# SW6208_A_B_C_L_LED__188.net
KiCad netlist of a schematic drawn in Altium Designer
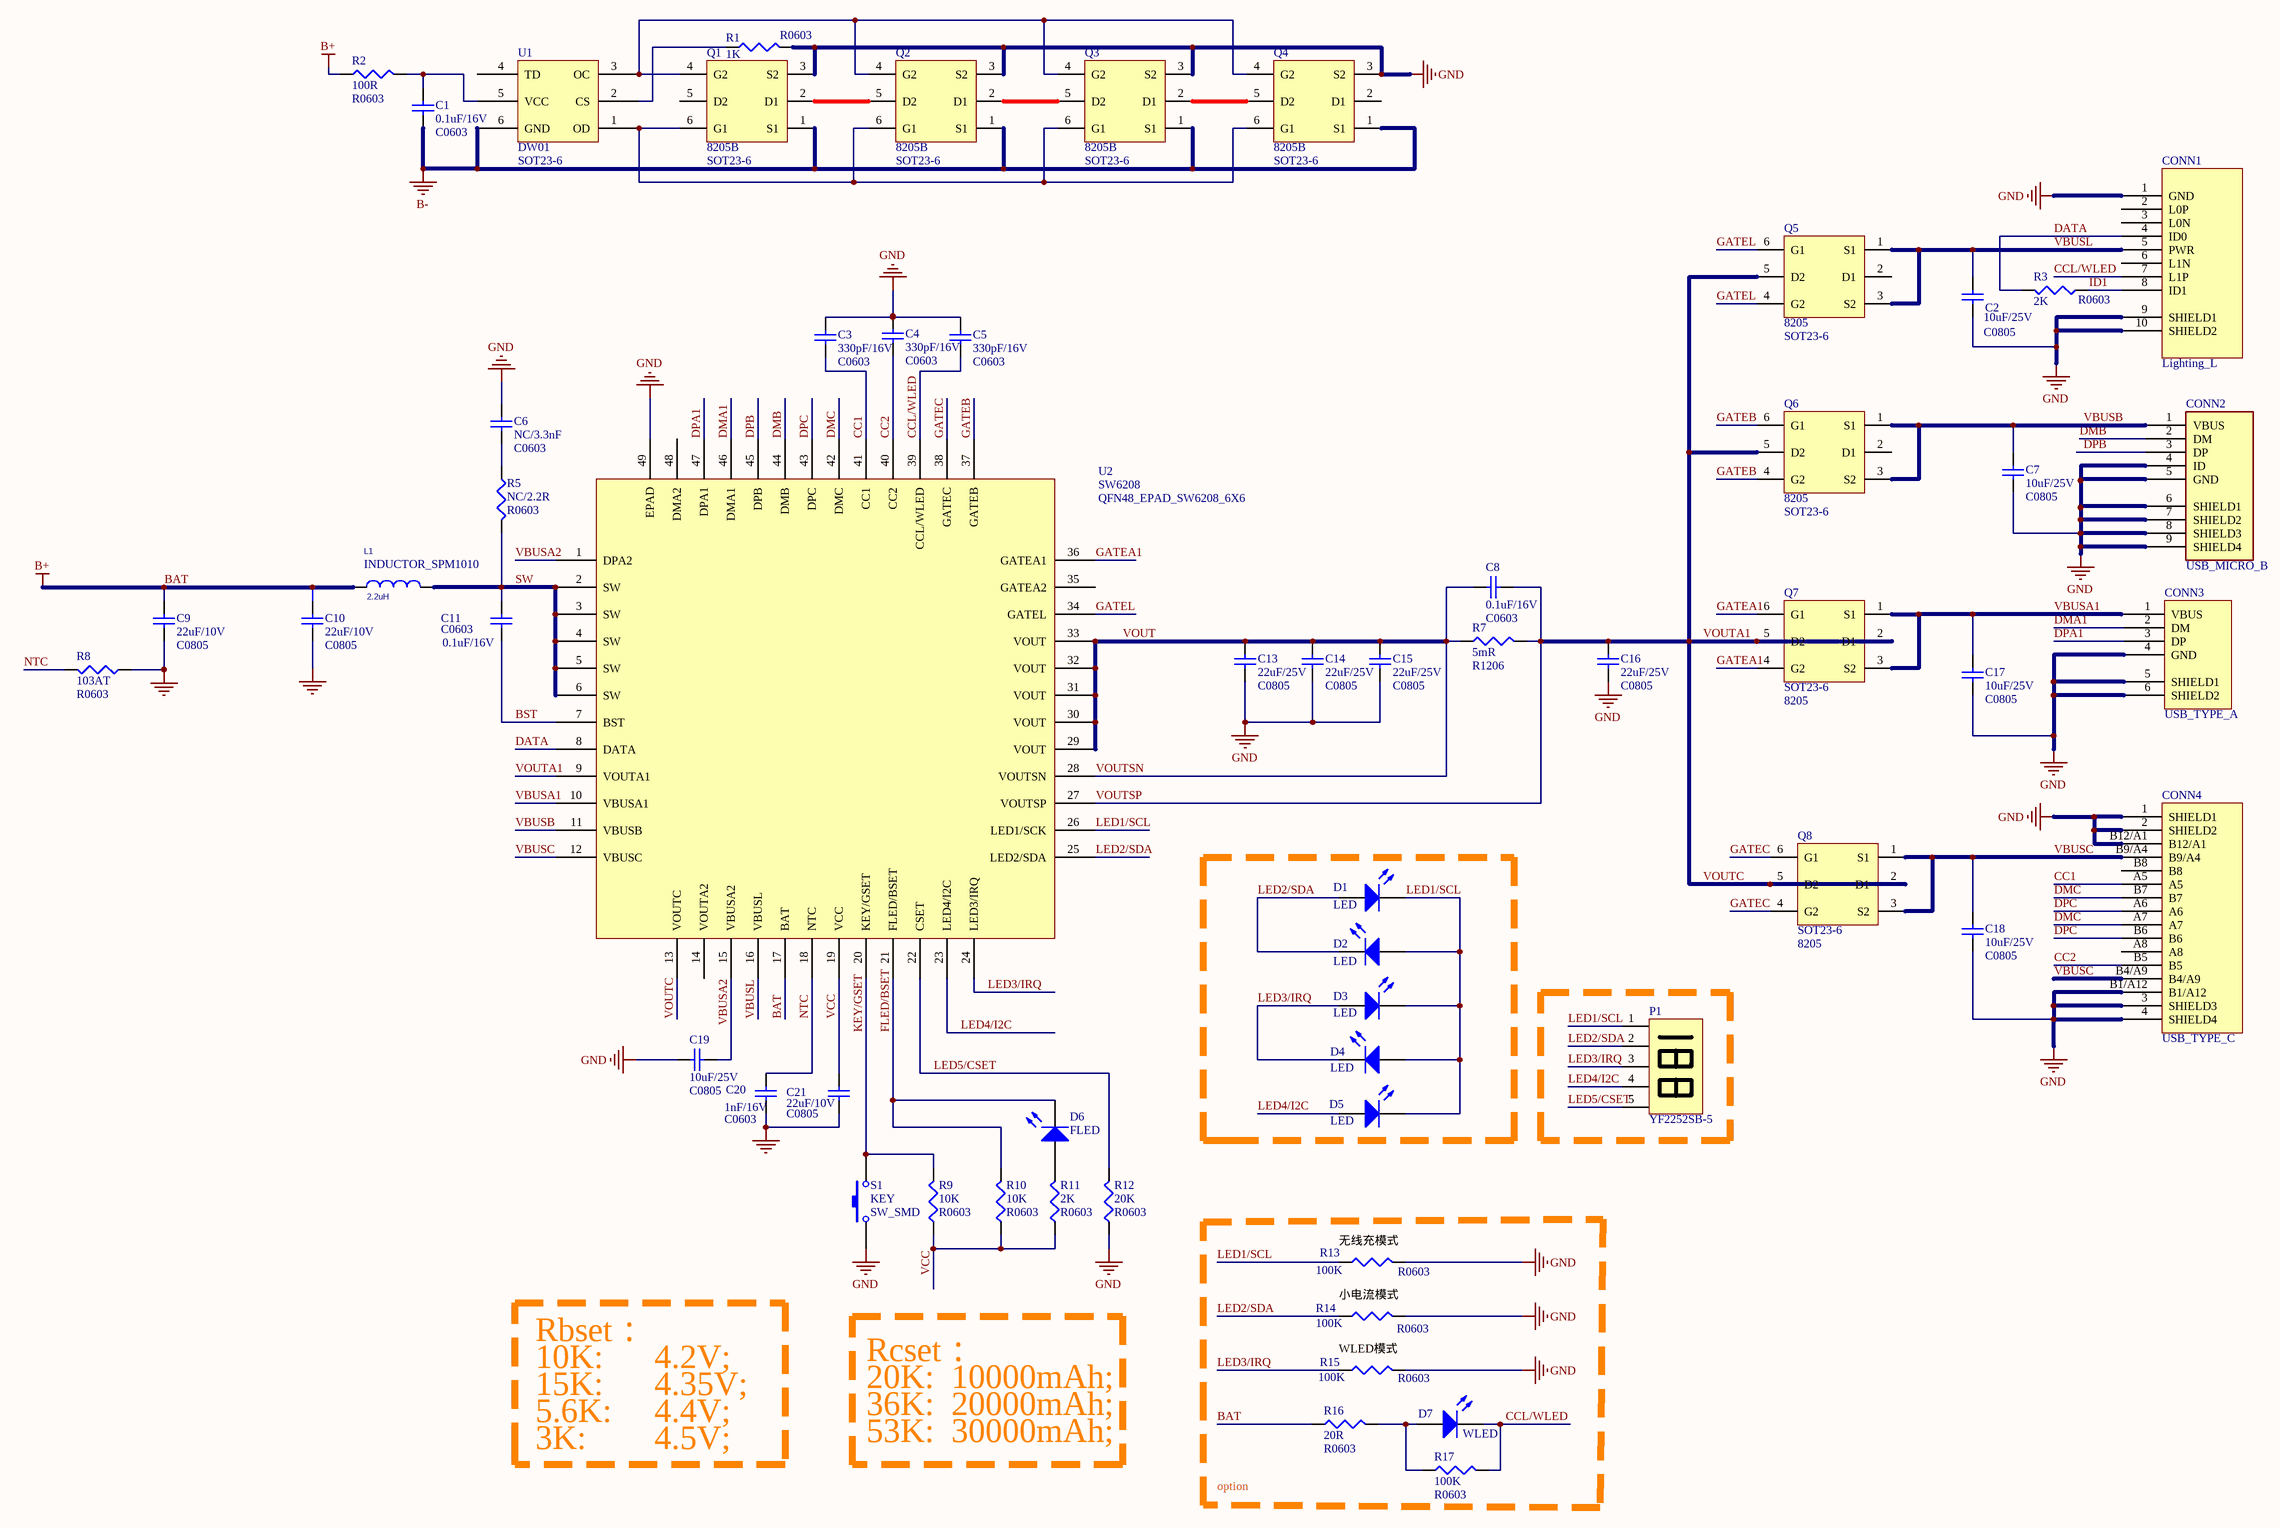
[diagram p0: SW6208+A+B+C+L+LED_普通188数码管.SchDoc]

(export (version "E")
  (design (tool "Eeschema 10.0.6"))
  (components
    (comp (ref "C1")
      (value "0.1uF/16V")
      (footprint "C0603")
      (description "Capacitor")
      (fields (field (name "PUBLISHER") "Altium Limited"))
      (libsource (lib "参考设计器件原理图更新") (part "CAP0603"))
    )
    (comp (ref "C2")
      (value "10uF/25V")
      (footprint "C0805")
      (description "Capacitor")
      (fields (field (name "PUBLISHER") "Altium Limited"))
      (libsource (lib "参考设计器件原理图更新") (part "CAP0805"))
    )
    (comp (ref "C3")
      (value "330pF/16V")
      (footprint "C0603")
      (description "Capacitor")
      (fields (field (name "PUBLISHER") "Altium Limited"))
      (libsource (lib "参考设计器件原理图更新") (part "CAP0603"))
    )
    (comp (ref "C4")
      (value "330pF/16V")
      (footprint "C0603")
      (description "Capacitor")
      (fields (field (name "PUBLISHER") "Altium Limited"))
      (libsource (lib "参考设计器件原理图更新") (part "CAP0603"))
    )
    (comp (ref "C5")
      (value "330pF/16V")
      (footprint "C0603")
      (description "Capacitor")
      (fields (field (name "PUBLISHER") "Altium Limited"))
      (libsource (lib "参考设计器件原理图更新") (part "CAP0603"))
    )
    (comp (ref "C6")
      (value "NC/3.3nF")
      (footprint "C0603")
      (description "Capacitor")
      (fields (field (name "PUBLISHER") "Altium Limited"))
      (libsource (lib "参考设计器件原理图更新") (part "CAP0603"))
    )
    (comp (ref "C7")
      (value "10uF/25V")
      (footprint "C0805")
      (description "Capacitor")
      (fields (field (name "PUBLISHER") "Altium Limited"))
      (libsource (lib "参考设计器件原理图更新") (part "CAP0805"))
    )
    (comp (ref "C8")
      (value "0.1uF/16V")
      (footprint "C0603")
      (description "Capacitor")
      (fields (field (name "PUBLISHER") "Altium Limited"))
      (libsource (lib "参考设计器件原理图更新") (part "CAP0603"))
    )
    (comp (ref "C9")
      (value "22uF/10V")
      (footprint "C0805")
      (description "Capacitor")
      (fields (field (name "PUBLISHER") "Altium Limited"))
      (libsource (lib "参考设计器件原理图更新") (part "CAP0805"))
    )
    (comp (ref "C10")
      (value "22uF/10V")
      (footprint "C0805")
      (description "Capacitor")
      (fields (field (name "PUBLISHER") "Altium Limited"))
      (libsource (lib "参考设计器件原理图更新") (part "CAP0805"))
    )
    (comp (ref "C11")
      (value "0.1uF/16V")
      (footprint "C0603")
      (description "Capacitor")
      (fields (field (name "PUBLISHER") "Altium Limited"))
      (libsource (lib "参考设计器件原理图更新") (part "CAP0603"))
    )
    (comp (ref "C13")
      (value "22uF/25V")
      (footprint "C0805")
      (description "Capacitor")
      (fields (field (name "PUBLISHER") "Altium Limited"))
      (libsource (lib "参考设计器件原理图更新") (part "CAP0805"))
    )
    (comp (ref "C14")
      (value "22uF/25V")
      (footprint "C0805")
      (description "Capacitor")
      (fields (field (name "PUBLISHER") "Altium Limited"))
      (libsource (lib "参考设计器件原理图更新") (part "CAP0805"))
    )
    (comp (ref "C15")
      (value "22uF/25V")
      (footprint "C0805")
      (description "Capacitor")
      (fields (field (name "PUBLISHER") "Altium Limited"))
      (libsource (lib "参考设计器件原理图更新") (part "CAP0805"))
    )
    (comp (ref "C16")
      (value "22uF/25V")
      (footprint "C0805")
      (description "Capacitor")
      (fields (field (name "PUBLISHER") "Altium Limited"))
      (libsource (lib "参考设计器件原理图更新") (part "CAP0805"))
    )
    (comp (ref "C17")
      (value "10uF/25V")
      (footprint "C0805")
      (description "Capacitor")
      (fields (field (name "PUBLISHER") "Altium Limited"))
      (libsource (lib "参考设计器件原理图更新") (part "CAP0805"))
    )
    (comp (ref "C18")
      (value "10uF/25V")
      (footprint "C0805")
      (description "Capacitor")
      (fields (field (name "PUBLISHER") "Altium Limited"))
      (libsource (lib "参考设计器件原理图更新") (part "CAP0805"))
    )
    (comp (ref "C19")
      (value "10uF/25V")
      (footprint "C0805")
      (description "Capacitor")
      (fields (field (name "PUBLISHER") "Altium Limited"))
      (libsource (lib "参考设计器件原理图更新") (part "CAP0805"))
    )
    (comp (ref "C20")
      (value "1nF/16V")
      (footprint "C0603")
      (description "Capacitor")
      (fields (field (name "PUBLISHER") "Altium Limited"))
      (libsource (lib "参考设计器件原理图更新") (part "CAP0603"))
    )
    (comp (ref "C21")
      (value "22uF/10V")
      (footprint "C0805")
      (description "Capacitor")
      (fields (field (name "PUBLISHER") "Altium Limited"))
      (libsource (lib "参考设计器件原理图更新") (part "CAP0805"))
    )
    (comp (ref "CONN1")
      (value "Lighting_L")
      (footprint "Lighting")
      (libsource (lib "参考设计器件原理图更新") (part "LIGHTING_PORT"))
    )
    (comp (ref "CONN2")
      (value "USB_MICRO_B")
      (footprint "USB_MICRO_B")
      (libsource (lib "参考设计器件原理图更新") (part "USB_MICRO_B"))
    )
    (comp (ref "CONN3")
      (value "USB_TYPE_A")
      (footprint "USB_TYPE_A")
      (libsource (lib "参考设计器件原理图更新") (part "USB_TYPE_A"))
    )
    (comp (ref "CONN4")
      (value "USB_TYPE_C")
      (footprint "LOUISAD:USB_TYPE_C")
      (libsource (lib "参考设计器件原理图更新") (part "USB_TYPE_C"))
    )
    (comp (ref "D1")
      (value "LED")
      (footprint "LED0603")
      (fields (field (name "PUBLISHER") "Altium Limited"))
      (libsource (lib "参考设计器件原理图更新") (part "LED_0603"))
    )
    (comp (ref "D2")
      (value "LED")
      (footprint "LED0603")
      (fields (field (name "PUBLISHER") "Altium Limited"))
      (libsource (lib "参考设计器件原理图更新") (part "LED_0603"))
    )
    (comp (ref "D3")
      (value "LED")
      (footprint "LED0603")
      (fields (field (name "PUBLISHER") "Altium Limited"))
      (libsource (lib "参考设计器件原理图更新") (part "LED_0603"))
    )
    (comp (ref "D4")
      (value "LED")
      (footprint "LED0603")
      (fields (field (name "PUBLISHER") "Altium Limited"))
      (libsource (lib "参考设计器件原理图更新") (part "LED_0603"))
    )
    (comp (ref "D5")
      (value "LED")
      (footprint "LED0603")
      (fields (field (name "PUBLISHER") "Altium Limited"))
      (libsource (lib "参考设计器件原理图更新") (part "LED_0603"))
    )
    (comp (ref "D6")
      (value "FLED")
      (footprint "LED0603")
      (description "LED")
      (fields (field (name "PUBLISHER") "Altium Limited"))
      (libsource (lib "参考设计器件原理图更新") (part "LED_0603"))
    )
    (comp (ref "D7")
      (value "WLED")
      (footprint "LED_5MM")
      (fields (field (name "PUBLISHER") "Altium Limited"))
      (libsource (lib "参考设计器件原理图更新") (part "WLED"))
    )
    (comp (ref "L1")
      (value "2.2uH")
      (footprint "INDUCTOR_SPM1010")
      (description "INDUCTOR")
      (libsource (lib "参考设计器件原理图更新") (part "INDUCTOR_SPM1010"))
    )
    (comp (ref "P1")
      (value "YF2252SB-5")
      (footprint "LED_Display_5")
      (description "188_LED_Display")
      (libsource (lib "参考设计器件原理图更新") (part "LED_Display_5"))
    )
    (comp (ref "Q1")
      (value "8205B")
      (footprint "SOT23-6")
      (description "NMOS")
      (fields (field (name "FOOTPRINF") "SOT23-6"))
      (libsource (lib "") (part "8205_1"))
    )
    (comp (ref "Q2")
      (value "8205B")
      (footprint "SOT23-6")
      (description "NMOS")
      (fields (field (name "FOOTPRINF") "SOT23-6"))
      (libsource (lib "") (part "8205_1"))
    )
    (comp (ref "Q3")
      (value "8205B")
      (footprint "SOT23-6")
      (description "NMOS")
      (fields (field (name "FOOTPRINF") "SOT23-6"))
      (libsource (lib "") (part "8205_1"))
    )
    (comp (ref "Q4")
      (value "8205B")
      (footprint "SOT23-6")
      (description "NMOS")
      (fields (field (name "FOOTPRINF") "SOT23-6"))
      (libsource (lib "") (part "8205_1"))
    )
    (comp (ref "Q5")
      (value "8205")
      (footprint "SOT23-6")
      (description "NMOS")
      (fields (field (name "FOOTPRINF") "SOT23-6"))
      (libsource (lib "参考设计器件原理图更新") (part "8205"))
    )
    (comp (ref "Q6")
      (value "8205")
      (footprint "SOT23-6")
      (description "NMOS")
      (fields (field (name "FOOTPRINF") "SOT23-6"))
      (libsource (lib "参考设计器件原理图更新") (part "8205"))
    )
    (comp (ref "Q7")
      (value "8205")
      (footprint "SOT-23-6")
      (fields (field (name "FOOTPRINF") "SOT23-6"))
      (libsource (lib "*") (part "8205B"))
    )
    (comp (ref "Q8")
      (value "8205")
      (footprint "SOT-23-6")
      (fields (field (name "FOOTPRINF") "SOT23-6"))
      (libsource (lib "*") (part "8205B"))
    )
    (comp (ref "R1")
      (value "1K")
      (footprint "R0603")
      (description "Resistor")
      (fields (field (name "PUBLISHER") "Altium Limited"))
      (libsource (lib "参考设计器件原理图更新") (part "RES_0603"))
    )
    (comp (ref "R2")
      (value "100R")
      (footprint "R0603")
      (description "Resistor")
      (fields (field (name "PUBLISHER") "Altium Limited"))
      (libsource (lib "参考设计器件原理图更新") (part "RES_0603"))
    )
    (comp (ref "R3")
      (value "2K")
      (footprint "R0603")
      (description "Resistor")
      (fields (field (name "PUBLISHER") "Altium Limited"))
      (libsource (lib "参考设计器件原理图更新") (part "RES_0603"))
    )
    (comp (ref "R5")
      (value "NC/2.2R")
      (footprint "R0603")
      (description "Resistor")
      (fields (field (name "PUBLISHER") "Altium Limited"))
      (libsource (lib "参考设计器件原理图更新") (part "RES_0603"))
    )
    (comp (ref "R7")
      (value "5mR")
      (footprint "R1206")
      (description "Resistor")
      (fields (field (name "PUBLISHER") "Altium Limited"))
      (libsource (lib "参考设计器件原理图更新") (part "RES_1206"))
    )
    (comp (ref "R8")
      (value "103AT")
      (footprint "R0603")
      (description "Resistor")
      (fields (field (name "PUBLISHER") "Altium Limited"))
      (libsource (lib "参考设计器件原理图更新") (part "RES_0603"))
    )
    (comp (ref "R9")
      (value "10K")
      (footprint "R0603")
      (description "Resistor")
      (fields (field (name "PUBLISHER") "Altium Limited"))
      (libsource (lib "参考设计器件原理图更新") (part "RES_0603"))
    )
    (comp (ref "R10")
      (value "10K")
      (footprint "R0603")
      (description "Resistor")
      (fields (field (name "PUBLISHER") "Altium Limited"))
      (libsource (lib "参考设计器件原理图更新") (part "RES_0603"))
    )
    (comp (ref "R11")
      (value "2K")
      (footprint "R0603")
      (description "Resistor")
      (fields (field (name "PUBLISHER") "Altium Limited"))
      (libsource (lib "参考设计器件原理图更新") (part "RES_0603"))
    )
    (comp (ref "R12")
      (value "20K")
      (footprint "R0603")
      (description "Resistor")
      (fields (field (name "PUBLISHER") "Altium Limited"))
      (libsource (lib "参考设计器件原理图更新") (part "RES_0603"))
    )
    (comp (ref "R13")
      (value "100K")
      (footprint "R0603")
      (description "Resistor")
      (fields (field (name "PUBLISHER") "Altium Limited"))
      (libsource (lib "参考设计器件原理图更新") (part "RES_0603"))
    )
    (comp (ref "R14")
      (value "100K")
      (footprint "R0603")
      (description "Resistor")
      (fields (field (name "PUBLISHER") "Altium Limited"))
      (libsource (lib "参考设计器件原理图更新") (part "RES_0603"))
    )
    (comp (ref "R15")
      (value "100K")
      (footprint "R0603")
      (description "Resistor")
      (fields (field (name "PUBLISHER") "Altium Limited"))
      (libsource (lib "参考设计器件原理图更新") (part "RES_0603"))
    )
    (comp (ref "R16")
      (value "20R")
      (footprint "R0603")
      (description "Resistor")
      (fields (field (name "PUBLISHER") "Altium Limited"))
      (libsource (lib "参考设计器件原理图更新") (part "RES_0603"))
    )
    (comp (ref "R17")
      (value "100K")
      (footprint "R0603")
      (description "Resistor")
      (fields (field (name "PUBLISHER") "Altium Limited"))
      (libsource (lib "参考设计器件原理图更新") (part "RES_0603"))
    )
    (comp (ref "S1")
      (value "KEY")
      (footprint "SW_SMD")
      (fields (field (name "FOOTPRINF") "SW_SMD"))
      (libsource (lib "参考设计器件原理图更新") (part "SW K"))
    )
    (comp (ref "U1")
      (value "DW01")
      (footprint "SOT23-6")
      (description "BAT_PROTECT_IC")
      (libsource (lib "参考设计器件原理图更新") (part "DW01"))
    )
    (comp (ref "U2")
      (value "SW6208")
      (footprint "QFN48_EPAD_SW6208_6X6")
      (description "IC")
      (libsource (lib "芯片型号原理图") (part "SW6208"))
    )
  )
  (nets
    (net (code "1") (name "/BST") (class "Default")
      (node (ref "C11") (pin "1") (pinfunction "1_1") (pintype "passive"))
      (node (ref "U2") (pin "7") (pinfunction "BST_7") (pintype "passive"))
    )
    (net (code "2") (name "/CC1") (class "Default")
      (node (ref "C3") (pin "1") (pinfunction "1_1") (pintype "passive"))
      (node (ref "CONN4") (pin "A5") (pinfunction "A5_A5") (pintype "passive"))
      (node (ref "U2") (pin "41") (pinfunction "CC1_41") (pintype "passive"))
    )
    (net (code "3") (name "/CC2") (class "Default")
      (node (ref "C4") (pin "1") (pinfunction "1_1") (pintype "passive"))
      (node (ref "CONN4") (pin "B5") (pinfunction "B5_B5") (pintype "passive"))
      (node (ref "U2") (pin "40") (pinfunction "CC2_40") (pintype "passive"))
    )
    (net (code "4") (name "/CCL{slash}WLED") (class "Default")
      (node (ref "C5") (pin "1") (pinfunction "1_1") (pintype "passive"))
      (node (ref "CONN1") (pin "7") (pinfunction "L1P_7") (pintype "passive"))
      (node (ref "D7") (pin "2") (pinfunction "K_2") (pintype "passive"))
      (node (ref "R17") (pin "2") (pinfunction "2_2") (pintype "passive"))
      (node (ref "U2") (pin "39") (pinfunction "CCL/WLED_39") (pintype "passive"))
    )
    (net (code "5") (name "/DATA") (class "Default")
      (node (ref "CONN1") (pin "4") (pinfunction "ID0_4") (pintype "passive"))
      (node (ref "R3") (pin "2") (pinfunction "2_2") (pintype "passive"))
      (node (ref "U2") (pin "8") (pinfunction "DATA_8") (pintype "passive"))
    )
    (net (code "6") (name "/DMA1") (class "Default")
      (node (ref "CONN3") (pin "2") (pinfunction "DM_2") (pintype "passive"))
      (node (ref "U2") (pin "46") (pinfunction "DMA1_46") (pintype "passive"))
    )
    (net (code "7") (name "/DMB") (class "Default")
      (node (ref "CONN2") (pin "2") (pinfunction "DM_2") (pintype "passive"))
      (node (ref "U2") (pin "44") (pinfunction "DMB_44") (pintype "passive"))
    )
    (net (code "8") (name "/DMC") (class "Default")
      (node (ref "CONN4") (pin "A7") (pinfunction "A7_A7") (pintype "passive"))
      (node (ref "CONN4") (pin "B7") (pinfunction "B7_B7") (pintype "passive"))
      (node (ref "U2") (pin "42") (pinfunction "DMC_42") (pintype "passive"))
    )
    (net (code "9") (name "/DPA1") (class "Default")
      (node (ref "CONN3") (pin "3") (pinfunction "DP_3") (pintype "passive"))
      (node (ref "U2") (pin "47") (pinfunction "DPA1_47") (pintype "passive"))
    )
    (net (code "10") (name "/DPB") (class "Default")
      (node (ref "CONN2") (pin "3") (pinfunction "DP_3") (pintype "passive"))
      (node (ref "U2") (pin "45") (pinfunction "DPB_45") (pintype "passive"))
    )
    (net (code "11") (name "/DPC") (class "Default")
      (node (ref "CONN4") (pin "A6") (pinfunction "A6_A6") (pintype "passive"))
      (node (ref "CONN4") (pin "B6") (pinfunction "B6_B6") (pintype "passive"))
      (node (ref "U2") (pin "43") (pinfunction "DPC_43") (pintype "passive"))
    )
    (net (code "12") (name "/FLED{slash}BSET") (class "Default")
      (node (ref "D6") (pin "2") (pinfunction "K_2") (pintype "passive"))
      (node (ref "R10") (pin "2") (pinfunction "2_2") (pintype "passive"))
      (node (ref "U2") (pin "21") (pinfunction "FLED/BSET_21") (pintype "passive"))
    )
    (net (code "13") (name "/GATEA1") (class "Default")
      (node (ref "Q7") (pin "4") (pinfunction "G2_4") (pintype "passive"))
      (node (ref "Q7") (pin "6") (pinfunction "G1_6") (pintype "passive"))
      (node (ref "U2") (pin "36") (pinfunction "GATEA1_36") (pintype "passive"))
    )
    (net (code "14") (name "/GATEB") (class "Default")
      (node (ref "Q6") (pin "4") (pinfunction "G2_4") (pintype "passive"))
      (node (ref "Q6") (pin "6") (pinfunction "G1_6") (pintype "passive"))
      (node (ref "U2") (pin "37") (pinfunction "GATEB_37") (pintype "passive"))
    )
    (net (code "15") (name "/GATEC") (class "Default")
      (node (ref "Q8") (pin "4") (pinfunction "G2_4") (pintype "passive"))
      (node (ref "Q8") (pin "6") (pinfunction "G1_6") (pintype "passive"))
      (node (ref "U2") (pin "38") (pinfunction "GATEC_38") (pintype "passive"))
    )
    (net (code "16") (name "/GATEL") (class "Default")
      (node (ref "Q5") (pin "4") (pinfunction "G2_4") (pintype "passive"))
      (node (ref "Q5") (pin "6") (pinfunction "G1_6") (pintype "passive"))
      (node (ref "U2") (pin "34") (pinfunction "GATEL_34") (pintype "passive"))
    )
    (net (code "17") (name "/ID1") (class "Default")
      (node (ref "CONN1") (pin "8") (pinfunction "ID1_8") (pintype "passive"))
      (node (ref "R3") (pin "1") (pinfunction "1_1") (pintype "passive"))
    )
    (net (code "18") (name "/KEY{slash}GSET") (class "Default")
      (node (ref "R9") (pin "2") (pinfunction "2_2") (pintype "passive"))
      (node (ref "S1") (pin "2") (pinfunction "2_2") (pintype "passive"))
      (node (ref "U2") (pin "20") (pinfunction "KEY/GSET_20") (pintype "passive"))
    )
    (net (code "19") (name "/LED1{slash}SCL") (class "Default")
      (node (ref "D1") (pin "2") (pinfunction "K_2") (pintype "passive"))
      (node (ref "D2") (pin "1") (pinfunction "A_1") (pintype "passive"))
      (node (ref "D3") (pin "2") (pinfunction "K_2") (pintype "passive"))
      (node (ref "D4") (pin "1") (pinfunction "A_1") (pintype "passive"))
      (node (ref "D5") (pin "2") (pinfunction "K_2") (pintype "passive"))
      (node (ref "P1") (pin "1") (pinfunction "F_1") (pintype "passive"))
      (node (ref "R13") (pin "1") (pinfunction "1_1") (pintype "passive"))
      (node (ref "U2") (pin "26") (pinfunction "LED1/SCK_26") (pintype "passive"))
    )
    (net (code "20") (name "/LED2{slash}SDA") (class "Default")
      (node (ref "D1") (pin "1") (pinfunction "A_1") (pintype "passive"))
      (node (ref "D2") (pin "2") (pinfunction "K_2") (pintype "passive"))
      (node (ref "P1") (pin "2") (pinfunction "C_2") (pintype "passive"))
      (node (ref "R14") (pin "1") (pinfunction "1_1") (pintype "passive"))
      (node (ref "U2") (pin "25") (pinfunction "LED2/SDA_25") (pintype "passive"))
    )
    (net (code "21") (name "/LED3{slash}IRQ") (class "Default")
      (node (ref "D3") (pin "1") (pinfunction "A_1") (pintype "passive"))
      (node (ref "D4") (pin "2") (pinfunction "K_2") (pintype "passive"))
      (node (ref "P1") (pin "3") (pinfunction "D_3") (pintype "passive"))
      (node (ref "R15") (pin "1") (pinfunction "1_1") (pintype "passive"))
      (node (ref "U2") (pin "24") (pinfunction "LED3/IRQ_24") (pintype "passive"))
    )
    (net (code "22") (name "/LED4{slash}I2C") (class "Default")
      (node (ref "D5") (pin "1") (pinfunction "A_1") (pintype "passive"))
      (node (ref "P1") (pin "4") (pinfunction "E_4") (pintype "passive"))
      (node (ref "U2") (pin "23") (pinfunction "LED4/I2C_23") (pintype "passive"))
    )
    (net (code "23") (name "/LED5{slash}CSET") (class "Default")
      (node (ref "P1") (pin "5") (pinfunction "G_5") (pintype "passive"))
      (node (ref "R12") (pin "2") (pinfunction "2_2") (pintype "passive"))
      (node (ref "U2") (pin "22") (pinfunction "CSET_22") (pintype "passive"))
    )
    (net (code "24") (name "/NTC") (class "Default")
      (node (ref "C20") (pin "1") (pinfunction "1_1") (pintype "passive"))
      (node (ref "R8") (pin "2") (pinfunction "2_2") (pintype "passive"))
      (node (ref "U2") (pin "18") (pinfunction "NTC_18") (pintype "passive"))
    )
    (net (code "25") (name "/SW") (class "Default")
      (node (ref "C11") (pin "2") (pinfunction "2_2") (pintype "passive"))
      (node (ref "L1") (pin "2") (pinfunction "2_2") (pintype "passive"))
      (node (ref "R5") (pin "2") (pinfunction "2_2") (pintype "passive"))
      (node (ref "U2") (pin "2") (pinfunction "SW_2") (pintype "passive"))
      (node (ref "U2") (pin "3") (pinfunction "SW_3") (pintype "passive"))
      (node (ref "U2") (pin "4") (pinfunction "SW_4") (pintype "passive"))
      (node (ref "U2") (pin "5") (pinfunction "SW_5") (pintype "passive"))
      (node (ref "U2") (pin "6") (pinfunction "SW_6") (pintype "passive"))
    )
    (net (code "26") (name "/VBUSA1") (class "Default")
      (node (ref "C17") (pin "2") (pinfunction "2_2") (pintype "passive"))
      (node (ref "Q7") (pin "1") (pinfunction "S1_1") (pintype "passive"))
      (node (ref "Q7") (pin "3") (pinfunction "S2_3") (pintype "passive"))
      (node (ref "U2") (pin "10") (pinfunction "VBUSA1_10") (pintype "passive"))
    )
    (net (code "27") (name "/VBUSA2") (class "Default")
      (node (ref "C19") (pin "2") (pinfunction "2_2") (pintype "passive"))
      (node (ref "U2") (pin "1") (pinfunction "DPA2_1") (pintype "passive"))
      (node (ref "U2") (pin "15") (pinfunction "VBUSA2_15") (pintype "passive"))
    )
    (net (code "28") (name "/VBUSB") (class "Default")
      (node (ref "C7") (pin "2") (pinfunction "2_2") (pintype "passive"))
      (node (ref "CONN2") (pin "1") (pinfunction "VBUS_1") (pintype "passive"))
      (node (ref "Q6") (pin "1") (pinfunction "S1_1") (pintype "passive"))
      (node (ref "Q6") (pin "3") (pinfunction "S2_3") (pintype "passive"))
      (node (ref "U2") (pin "11") (pinfunction "VBUSB_11") (pintype "passive"))
    )
    (net (code "29") (name "/VBUSC") (class "Default")
      (node (ref "C18") (pin "2") (pinfunction "2_2") (pintype "passive"))
      (node (ref "CONN4") (pin "B4/A9") (pinfunction "B4/A9_B4/A9") (pintype "passive"))
      (node (ref "CONN4") (pin "B9/A4") (pinfunction "B9/A4_B9/A4") (pintype "passive"))
      (node (ref "Q8") (pin "1") (pinfunction "S1_1") (pintype "passive"))
      (node (ref "Q8") (pin "3") (pinfunction "S2_3") (pintype "passive"))
      (node (ref "U2") (pin "12") (pinfunction "VBUSC_12") (pintype "passive"))
    )
    (net (code "30") (name "/VBUSL") (class "Default")
      (node (ref "C2") (pin "2") (pinfunction "2_2") (pintype "passive"))
      (node (ref "CONN1") (pin "5") (pinfunction "PWR_5") (pintype "passive"))
      (node (ref "Q5") (pin "1") (pinfunction "S1_1") (pintype "passive"))
      (node (ref "Q5") (pin "3") (pinfunction "S2_3") (pintype "passive"))
      (node (ref "U2") (pin "16") (pinfunction "VBUSL_16") (pintype "passive"))
    )
    (net (code "31") (name "/VCC") (class "Default")
      (node (ref "C21") (pin "1") (pinfunction "1_1") (pintype "passive"))
      (node (ref "R10") (pin "1") (pinfunction "1_1") (pintype "passive"))
      (node (ref "R11") (pin "1") (pinfunction "1_1") (pintype "passive"))
      (node (ref "R9") (pin "1") (pinfunction "1_1") (pintype "passive"))
      (node (ref "U2") (pin "19") (pinfunction "VCC_19") (pintype "passive"))
    )
    (net (code "32") (name "/VOUT") (class "Default")
      (node (ref "C13") (pin "2") (pinfunction "2_2") (pintype "passive"))
      (node (ref "C14") (pin "2") (pinfunction "2_2") (pintype "passive"))
      (node (ref "C15") (pin "2") (pinfunction "2_2") (pintype "passive"))
      (node (ref "C8") (pin "1") (pinfunction "1_1") (pintype "passive"))
      (node (ref "R7") (pin "1") (pinfunction "1_1") (pintype "passive"))
      (node (ref "U2") (pin "28") (pinfunction "VOUTSN_28") (pintype "passive"))
      (node (ref "U2") (pin "29") (pinfunction "VOUT_29") (pintype "passive"))
      (node (ref "U2") (pin "30") (pinfunction "VOUT_30") (pintype "passive"))
      (node (ref "U2") (pin "31") (pinfunction "VOUT_31") (pintype "passive"))
      (node (ref "U2") (pin "32") (pinfunction "VOUT_32") (pintype "passive"))
      (node (ref "U2") (pin "33") (pinfunction "VOUT_33") (pintype "passive"))
    )
    (net (code "33") (name "/VOUTA1") (class "Default")
      (node (ref "C16") (pin "2") (pinfunction "2_2") (pintype "passive"))
      (node (ref "C8") (pin "2") (pinfunction "2_2") (pintype "passive"))
      (node (ref "Q5") (pin "5") (pinfunction "D2_5") (pintype "passive"))
      (node (ref "Q6") (pin "5") (pinfunction "D2_5") (pintype "passive"))
      (node (ref "Q7") (pin "2") (pinfunction "D1_2") (pintype "passive"))
      (node (ref "Q7") (pin "5") (pinfunction "D2_5") (pintype "passive"))
      (node (ref "Q8") (pin "2") (pinfunction "D1_2") (pintype "passive"))
      (node (ref "Q8") (pin "5") (pinfunction "D2_5") (pintype "passive"))
      (node (ref "R7") (pin "2") (pinfunction "2_2") (pintype "passive"))
      (node (ref "U2") (pin "13") (pinfunction "VOUTC_13") (pintype "passive"))
      (node (ref "U2") (pin "27") (pinfunction "VOUTSP_27") (pintype "passive"))
      (node (ref "U2") (pin "9") (pinfunction "VOUTA1_9") (pintype "passive"))
    )
    (net (code "34") (name "B+") (class "Default")
      (node (ref "C10") (pin "2") (pinfunction "2_2") (pintype "passive"))
      (node (ref "C9") (pin "2") (pinfunction "2_2") (pintype "passive"))
      (node (ref "L1") (pin "1") (pinfunction "1_1") (pintype "passive"))
      (node (ref "R16") (pin "1") (pinfunction "1_1") (pintype "passive"))
      (node (ref "R2") (pin "1") (pinfunction "1_1") (pintype "passive"))
      (node (ref "U2") (pin "17") (pinfunction "BAT_17") (pintype "passive"))
    )
    (net (code "35") (name "B-") (class "Default")
      (node (ref "C1") (pin "1") (pinfunction "1_1") (pintype "passive"))
      (node (ref "Q1") (pin "1") (pinfunction "S1_1") (pintype "passive"))
      (node (ref "Q2") (pin "1") (pinfunction "S1_1") (pintype "passive"))
      (node (ref "Q3") (pin "1") (pinfunction "S1_1") (pintype "passive"))
      (node (ref "Q4") (pin "1") (pinfunction "S1_1") (pintype "passive"))
      (node (ref "U1") (pin "6") (pinfunction "GND_6") (pintype "passive"))
    )
    (net (code "36") (name "GND") (class "Default")
      (node (ref "C10") (pin "1") (pinfunction "1_1") (pintype "passive"))
      (node (ref "C13") (pin "1") (pinfunction "1_1") (pintype "passive"))
      (node (ref "C14") (pin "1") (pinfunction "1_1") (pintype "passive"))
      (node (ref "C15") (pin "1") (pinfunction "1_1") (pintype "passive"))
      (node (ref "C16") (pin "1") (pinfunction "1_1") (pintype "passive"))
      (node (ref "C17") (pin "1") (pinfunction "1_1") (pintype "passive"))
      (node (ref "C18") (pin "1") (pinfunction "1_1") (pintype "passive"))
      (node (ref "C19") (pin "1") (pinfunction "1_1") (pintype "passive"))
      (node (ref "C2") (pin "1") (pinfunction "1_1") (pintype "passive"))
      (node (ref "C20") (pin "2") (pinfunction "2_2") (pintype "passive"))
      (node (ref "C21") (pin "2") (pinfunction "2_2") (pintype "passive"))
      (node (ref "C3") (pin "2") (pinfunction "2_2") (pintype "passive"))
      (node (ref "C4") (pin "2") (pinfunction "2_2") (pintype "passive"))
      (node (ref "C5") (pin "2") (pinfunction "2_2") (pintype "passive"))
      (node (ref "C6") (pin "2") (pinfunction "2_2") (pintype "passive"))
      (node (ref "C7") (pin "1") (pinfunction "1_1") (pintype "passive"))
      (node (ref "C9") (pin "1") (pinfunction "1_1") (pintype "passive"))
      (node (ref "CONN1") (pin "1") (pinfunction "GND_1") (pintype "passive"))
      (node (ref "CONN1") (pin "10") (pinfunction "SHIELD2_10") (pintype "passive"))
      (node (ref "CONN1") (pin "9") (pinfunction "SHIELD1_9") (pintype "passive"))
      (node (ref "CONN2") (pin "4") (pinfunction "ID_4") (pintype "passive"))
      (node (ref "CONN2") (pin "5") (pinfunction "GND_5") (pintype "passive"))
      (node (ref "CONN2") (pin "6") (pinfunction "SHIELD1_6") (pintype "passive"))
      (node (ref "CONN2") (pin "7") (pinfunction "SHIELD2_7") (pintype "passive"))
      (node (ref "CONN2") (pin "8") (pinfunction "SHIELD3_8") (pintype "passive"))
      (node (ref "CONN2") (pin "9") (pinfunction "SHIELD4_9") (pintype "passive"))
      (node (ref "CONN3") (pin "4") (pinfunction "GND_4") (pintype "passive"))
      (node (ref "CONN3") (pin "5") (pinfunction "SHIELD1_5") (pintype "passive"))
      (node (ref "CONN3") (pin "6") (pinfunction "SHIELD2_6") (pintype "passive"))
      (node (ref "CONN4") (pin "1") (pinfunction "SHIELD1_1") (pintype "passive"))
      (node (ref "CONN4") (pin "2") (pinfunction "SHIELD2_2") (pintype "passive"))
      (node (ref "CONN4") (pin "3") (pinfunction "SHIELD3_3") (pintype "passive"))
      (node (ref "CONN4") (pin "4") (pinfunction "SHIELD4_4") (pintype "passive"))
      (node (ref "CONN4") (pin "B1/A12") (pinfunction "B1/A12_B1/A12") (pintype "passive"))
      (node (ref "CONN4") (pin "B12/A1") (pinfunction "B12/A1_B12/A1") (pintype "passive"))
      (node (ref "Q1") (pin "3") (pinfunction "S2_3") (pintype "passive"))
      (node (ref "Q2") (pin "3") (pinfunction "S2_3") (pintype "passive"))
      (node (ref "Q3") (pin "3") (pinfunction "S2_3") (pintype "passive"))
      (node (ref "Q4") (pin "3") (pinfunction "S2_3") (pintype "passive"))
      (node (ref "R1") (pin "2") (pinfunction "2_2") (pintype "passive"))
      (node (ref "R12") (pin "1") (pinfunction "1_1") (pintype "passive"))
      (node (ref "R13") (pin "2") (pinfunction "2_2") (pintype "passive"))
      (node (ref "R14") (pin "2") (pinfunction "2_2") (pintype "passive"))
      (node (ref "R15") (pin "2") (pinfunction "2_2") (pintype "passive"))
      (node (ref "R8") (pin "1") (pinfunction "1_1") (pintype "passive"))
      (node (ref "S1") (pin "1") (pinfunction "1_1") (pintype "passive"))
      (node (ref "U2") (pin "49") (pinfunction "EPAD_49") (pintype "passive"))
    )
    (net (code "37") (name "Net-(C6-Pad1)") (class "Default")
      (node (ref "C6") (pin "1") (pinfunction "1_1") (pintype "passive"))
      (node (ref "R5") (pin "1") (pinfunction "1_1") (pintype "passive"))
    )
    (net (code "38") (name "Net-(D6-A)") (class "Default")
      (node (ref "D6") (pin "1") (pinfunction "A_1") (pintype "passive"))
      (node (ref "R11") (pin "2") (pinfunction "2_2") (pintype "passive"))
    )
    (net (code "39") (name "Net-(D7-A)") (class "Default")
      (node (ref "D7") (pin "1") (pinfunction "A_1") (pintype "passive"))
      (node (ref "R16") (pin "2") (pinfunction "2_2") (pintype "passive"))
      (node (ref "R17") (pin "1") (pinfunction "1_1") (pintype "passive"))
    )
    (net (code "40") (name "Net-(Q1-D1)") (class "Default")
      (node (ref "Q1") (pin "2") (pinfunction "D1_2") (pintype "passive"))
      (node (ref "Q2") (pin "5") (pinfunction "D2_5") (pintype "passive"))
    )
    (net (code "41") (name "Net-(Q1-G1)") (class "Default")
      (node (ref "Q1") (pin "6") (pinfunction "G1_6") (pintype "passive"))
      (node (ref "Q2") (pin "6") (pinfunction "G1_6") (pintype "passive"))
      (node (ref "Q3") (pin "6") (pinfunction "G1_6") (pintype "passive"))
      (node (ref "Q4") (pin "6") (pinfunction "G1_6") (pintype "passive"))
      (node (ref "U1") (pin "1") (pinfunction "OD_1") (pintype "passive"))
    )
    (net (code "42") (name "Net-(Q1-G2)") (class "Default")
      (node (ref "Q1") (pin "4") (pinfunction "G2_4") (pintype "passive"))
      (node (ref "Q2") (pin "4") (pinfunction "G2_4") (pintype "passive"))
      (node (ref "Q3") (pin "4") (pinfunction "G2_4") (pintype "passive"))
      (node (ref "Q4") (pin "4") (pinfunction "G2_4") (pintype "passive"))
      (node (ref "U1") (pin "3") (pinfunction "OC_3") (pintype "passive"))
    )
    (net (code "43") (name "Net-(Q2-D1)") (class "Default")
      (node (ref "Q2") (pin "2") (pinfunction "D1_2") (pintype "passive"))
      (node (ref "Q3") (pin "5") (pinfunction "D2_5") (pintype "passive"))
    )
    (net (code "44") (name "Net-(Q3-D1)") (class "Default")
      (node (ref "Q3") (pin "2") (pinfunction "D1_2") (pintype "passive"))
      (node (ref "Q4") (pin "5") (pinfunction "D2_5") (pintype "passive"))
    )
    (net (code "45") (name "Net-(U1-CS)") (class "Default")
      (node (ref "R1") (pin "1") (pinfunction "1_1") (pintype "passive"))
      (node (ref "U1") (pin "2") (pinfunction "CS_2") (pintype "passive"))
    )
    (net (code "46") (name "Net-(U1-VCC)") (class "Default")
      (node (ref "C1") (pin "2") (pinfunction "2_2") (pintype "passive"))
      (node (ref "R2") (pin "2") (pinfunction "2_2") (pintype "passive"))
      (node (ref "U1") (pin "5") (pinfunction "VCC_5") (pintype "passive"))
    )
    (net (code "47") (name "unconnected-(CONN1-L0N-Pad3)") (class "Default")
      (node (ref "CONN1") (pin "3") (pinfunction "L0N_3") (pintype "passive"))
    )
    (net (code "48") (name "unconnected-(CONN1-L0P-Pad2)") (class "Default")
      (node (ref "CONN1") (pin "2") (pinfunction "L0P_2") (pintype "passive"))
    )
    (net (code "49") (name "unconnected-(CONN1-L1N-Pad6)") (class "Default")
      (node (ref "CONN1") (pin "6") (pinfunction "L1N_6") (pintype "passive"))
    )
    (net (code "50") (name "unconnected-(CONN3-VBUS-Pad1)") (class "Default")
      (node (ref "CONN3") (pin "1") (pinfunction "VBUS_1") (pintype "passive"))
    )
    (net (code "51") (name "unconnected-(CONN4-PadA8)") (class "Default")
      (node (ref "CONN4") (pin "A8") (pinfunction "A8_A8") (pintype "passive"))
    )
    (net (code "52") (name "unconnected-(CONN4-PadB8)") (class "Default")
      (node (ref "CONN4") (pin "B8") (pinfunction "B8_B8") (pintype "passive"))
    )
    (net (code "53") (name "unconnected-(Q1-D2-Pad5)") (class "Default")
      (node (ref "Q1") (pin "5") (pinfunction "D2_5") (pintype "passive"))
    )
    (net (code "54") (name "unconnected-(Q4-D1-Pad2)") (class "Default")
      (node (ref "Q4") (pin "2") (pinfunction "D1_2") (pintype "passive"))
    )
    (net (code "55") (name "unconnected-(Q5-D1-Pad2)") (class "Default")
      (node (ref "Q5") (pin "2") (pinfunction "D1_2") (pintype "passive"))
    )
    (net (code "56") (name "unconnected-(Q6-D1-Pad2)") (class "Default")
      (node (ref "Q6") (pin "2") (pinfunction "D1_2") (pintype "passive"))
    )
    (net (code "57") (name "unconnected-(U1-TD-Pad4)") (class "Default")
      (node (ref "U1") (pin "4") (pinfunction "TD_4") (pintype "passive"))
    )
    (net (code "58") (name "unconnected-(U2-DMA2-Pad48)") (class "Default")
      (node (ref "U2") (pin "48") (pinfunction "DMA2_48") (pintype "passive"))
    )
    (net (code "59") (name "unconnected-(U2-GATEA2-Pad35)") (class "Default")
      (node (ref "U2") (pin "35") (pinfunction "GATEA2_35") (pintype "passive"))
    )
    (net (code "60") (name "unconnected-(U2-VOUTA2-Pad14)") (class "Default")
      (node (ref "U2") (pin "14") (pinfunction "VOUTA2_14") (pintype "passive"))
    )
  )
)
